# schematic.net
KiCad netlist of a schematic drawn in EAGLE
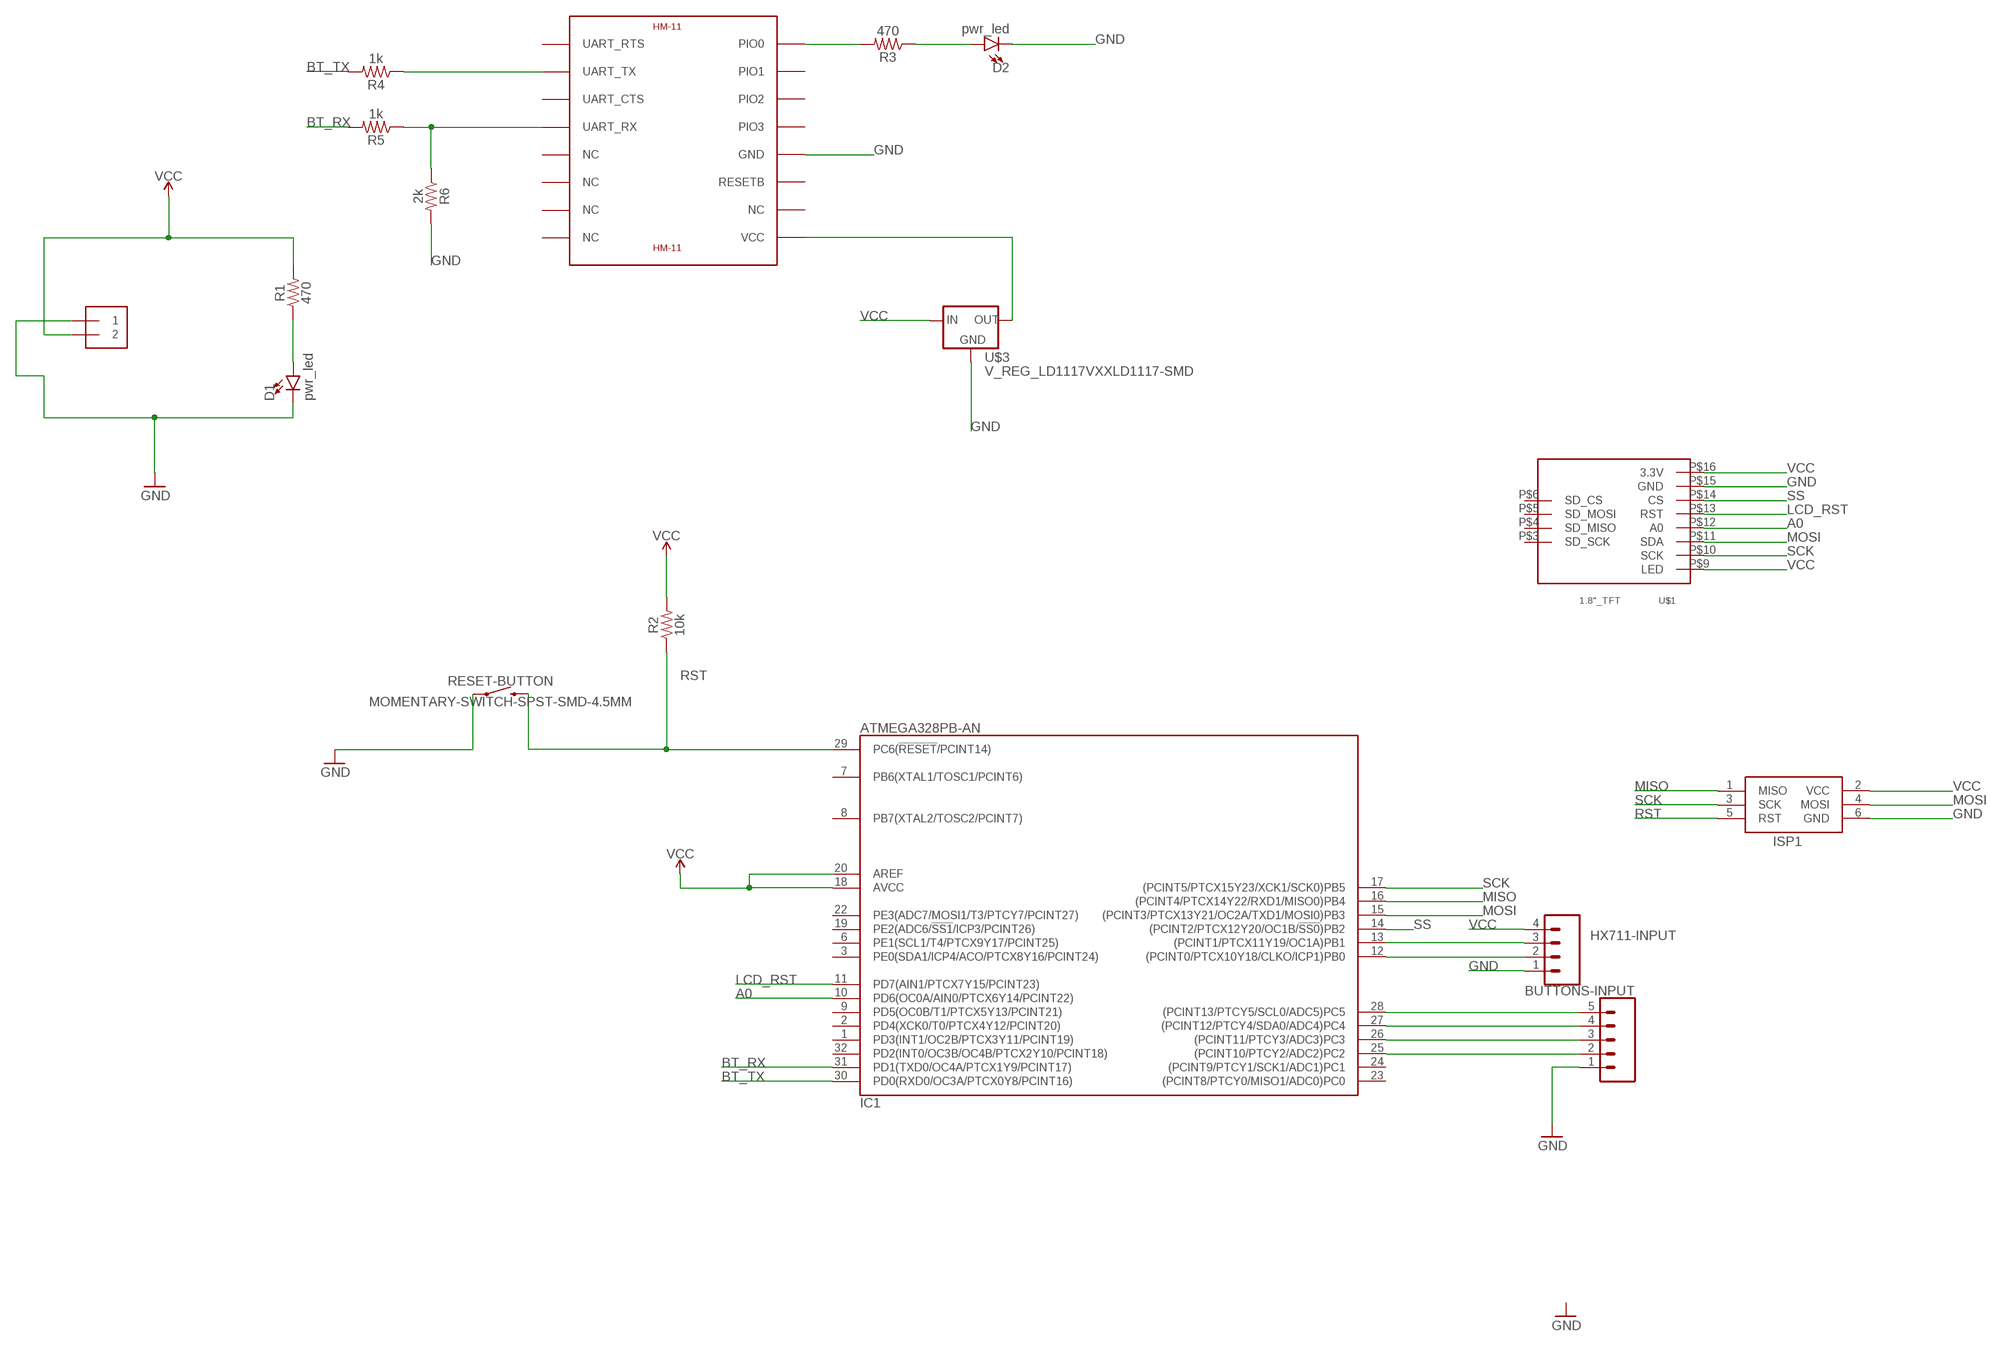
[diagram p0: schematic, sheet 1]

(export (version "E")
  (design (tool "Eeschema 10.0.6"))
  (components
    (comp (ref "BUTTONS-INPUT")
      (value "CONN_05")
      (footprint "eagle-import:1X05")
      (libsource (lib "eagle-import") (part "CONN_05"))
    )
    (comp (ref "D1")
      (value "pwr_led")
      (footprint "eagle-import:LED-1206")
      (libsource (lib "eagle-import") (part "LED1206"))
    )
    (comp (ref "D2")
      (value "pwr_led")
      (footprint "eagle-import:LED-1206")
      (libsource (lib "eagle-import") (part "LED1206"))
    )
    (comp (ref "HX711-INPUT")
      (value "CONN_04LONGPADS")
      (footprint "eagle-import:1X04_LONGPADS")
      (libsource (lib "eagle-import") (part "CONN_04LONGPADS"))
    )
    (comp (ref "IC1")
      (value "ATMEGA328PB-AN")
      (footprint "eagle-import:QFP32_7X7_0.80")
      (libsource (lib "eagle-import") (part "ATMEGA328PB-AN"))
    )
    (comp (ref "ISP1")
      (value "AVRISP-BOX")
      (footprint "eagle-import:AVRISP-BOX")
      (libsource (lib "eagle-import") (part "AVRISP-BOX"))
    )
    (comp (ref "PWR")
      (value "1X2-3.5MM")
      (footprint "eagle-import:1X2-3.5MM")
      (libsource (lib "eagle-import") (part "1X2-3.5MM"))
    )
    (comp (ref "R1")
      (value "470")
      (footprint "eagle-import:1206")
      (libsource (lib "eagle-import") (part "RESISTOR1206"))
    )
    (comp (ref "R2")
      (value "10k")
      (footprint "eagle-import:1206")
      (libsource (lib "eagle-import") (part "RESISTOR1206"))
    )
    (comp (ref "R3")
      (value "470")
      (footprint "eagle-import:1206")
      (libsource (lib "eagle-import") (part "RESISTOR1206"))
    )
    (comp (ref "R4")
      (value "1k")
      (footprint "eagle-import:1206")
      (libsource (lib "eagle-import") (part "RESISTOR1206"))
    )
    (comp (ref "R5")
      (value "1k")
      (footprint "eagle-import:1206")
      (libsource (lib "eagle-import") (part "RESISTOR1206"))
    )
    (comp (ref "R6")
      (value "2k")
      (footprint "eagle-import:1206")
      (libsource (lib "eagle-import") (part "RESISTOR1206"))
    )
    (comp (ref "RESET-BUTTON")
      (value "MOMENTARY-SWITCH-SPST-SMD-4.5MM")
      (footprint "eagle-import:TACTILE_SWITCH_SMD_4.5MM")
      (libsource (lib "eagle-import") (part "MOMENTARY-SWITCH-SPST-SMD-4.5MM"))
    )
    (comp (ref "U$1")
      (value "1.8\"_TFT")
      (footprint "eagle-import:1.8__TFT")
      (libsource (lib "eagle-import") (part "1.8{dblquote}_TFT"))
    )
    (comp (ref "U$2")
      (value "HM-11")
      (footprint "eagle-import:HM-11")
      (libsource (lib "eagle-import") (part "HM-11"))
    )
    (comp (ref "U$3")
      (value "V_REG_LD1117VXXLD1117-SMD")
      (footprint "eagle-import:SOT223")
      (libsource (lib "eagle-import") (part "V_REG_LD1117VXXLD1117-SMD"))
    )
  )
  (nets
    (net (code "1") (name "/A0") (class "Default")
      (node (ref "IC1") (pin "10") (pinfunction "PD6(OC0A/AIN0/PTCX6Y14/PCINT22)_10") (pintype "bidirectional"))
      (node (ref "U$1") (pin "P$12") (pinfunction "A0_P$12") (pintype "bidirectional"))
    )
    (net (code "2") (name "/BT_RX") (class "Default")
      (node (ref "IC1") (pin "31") (pinfunction "PD1(TXD0/OC4A/PTCX1Y9/PCINT17)_31") (pintype "bidirectional"))
      (node (ref "R5") (pin "2") (pinfunction "2_2") (pintype "passive"))
    )
    (net (code "3") (name "/BT_TX") (class "Default")
      (node (ref "IC1") (pin "30") (pinfunction "PD0(RXD0/OC3A/PTCX0Y8/PCINT16)_30") (pintype "bidirectional"))
      (node (ref "R4") (pin "2") (pinfunction "2_2") (pintype "passive"))
    )
    (net (code "4") (name "/LCD_RST") (class "Default")
      (node (ref "IC1") (pin "11") (pinfunction "PD7(AIN1/PTCX7Y15/PCINT23)_11") (pintype "bidirectional"))
      (node (ref "U$1") (pin "P$13") (pinfunction "RST_P$13") (pintype "bidirectional"))
    )
    (net (code "5") (name "/MISO") (class "Default")
      (node (ref "IC1") (pin "16") (pinfunction "(PCINT4/PTCX14Y22/RXD1/MISO0)PB4_16") (pintype "bidirectional"))
      (node (ref "ISP1") (pin "1") (pinfunction "MISO_1") (pintype "input"))
    )
    (net (code "6") (name "/MOSI") (class "Default")
      (node (ref "IC1") (pin "15") (pinfunction "(PCINT3/PTCX13Y21/OC2A/TXD1/MOSI0)PB3_15") (pintype "bidirectional"))
      (node (ref "ISP1") (pin "4") (pinfunction "MOSI_4") (pintype "output"))
      (node (ref "U$1") (pin "P$11") (pinfunction "SDA_P$11") (pintype "bidirectional"))
    )
    (net (code "7") (name "/RST") (class "Default")
      (node (ref "IC1") (pin "29") (pinfunction "PC6(~{RESET}/PCINT14)_29") (pintype "bidirectional"))
      (node (ref "ISP1") (pin "5") (pinfunction "RST_5") (pintype "output"))
      (node (ref "R2") (pin "1") (pinfunction "1_1") (pintype "passive"))
      (node (ref "RESET-BUTTON") (pin "1") (pinfunction "2_1") (pintype "passive"))
      (node (ref "RESET-BUTTON") (pin "4") (pinfunction "2_4") (pintype "passive"))
    )
    (net (code "8") (name "/SCK") (class "Default")
      (node (ref "IC1") (pin "17") (pinfunction "(PCINT5/PTCX15Y23/XCK1/SCK0)PB5_17") (pintype "bidirectional"))
      (node (ref "ISP1") (pin "3") (pinfunction "SCK_3") (pintype "output"))
      (node (ref "U$1") (pin "P$10") (pinfunction "SCK_P$10") (pintype "bidirectional"))
    )
    (net (code "9") (name "/SS") (class "Default")
      (node (ref "IC1") (pin "14") (pinfunction "(PCINT2/PTCX12Y20/OC1B/~{SS0})PB2_14") (pintype "bidirectional"))
      (node (ref "U$1") (pin "P$14") (pinfunction "CS_P$14") (pintype "bidirectional"))
    )
    (net (code "10") (name "GND") (class "Default")
      (node (ref "BUTTONS-INPUT") (pin "1") (pinfunction "1_1") (pintype "passive"))
      (node (ref "D1") (pin "C") (pinfunction "C_C") (pintype "passive"))
      (node (ref "D2") (pin "C") (pinfunction "C_C") (pintype "passive"))
      (node (ref "HX711-INPUT") (pin "1") (pinfunction "1_1") (pintype "passive"))
      (node (ref "ISP1") (pin "6") (pinfunction "GND_6") (pintype "power_in"))
      (node (ref "PWR") (pin "1") (pinfunction "1_1") (pintype "passive"))
      (node (ref "R6") (pin "2") (pinfunction "2_2") (pintype "passive"))
      (node (ref "RESET-BUTTON") (pin "2") (pinfunction "1_2") (pintype "passive"))
      (node (ref "RESET-BUTTON") (pin "3") (pinfunction "1_3") (pintype "passive"))
      (node (ref "U$1") (pin "P$15") (pinfunction "GND_P$15") (pintype "bidirectional"))
      (node (ref "U$2") (pin "GND") (pinfunction "GND_GND") (pintype "bidirectional"))
      (node (ref "U$3") (pin "1") (pinfunction "GND_1") (pintype "input"))
    )
    (net (code "11") (name "Net-(D1-PadA)") (class "Default")
      (node (ref "D1") (pin "A") (pinfunction "A_A") (pintype "passive"))
      (node (ref "R1") (pin "1") (pinfunction "1_1") (pintype "passive"))
    )
    (net (code "12") (name "Net-(D2-PadA)") (class "Default")
      (node (ref "D2") (pin "A") (pinfunction "A_A") (pintype "passive"))
      (node (ref "R3") (pin "1") (pinfunction "1_1") (pintype "passive"))
    )
    (net (code "13") (name "Net-(IC1A-(PCINT0{slash}PTCX10Y18{slash}CLKO{slash}ICP1)PB0)") (class "Default")
      (node (ref "HX711-INPUT") (pin "2") (pinfunction "2_2") (pintype "passive"))
      (node (ref "IC1") (pin "12") (pinfunction "(PCINT0/PTCX10Y18/CLKO/ICP1)PB0_12") (pintype "bidirectional"))
    )
    (net (code "14") (name "Net-(IC1A-(PCINT1{slash}PTCX11Y19{slash}OC1A)PB1)") (class "Default")
      (node (ref "HX711-INPUT") (pin "3") (pinfunction "3_3") (pintype "passive"))
      (node (ref "IC1") (pin "13") (pinfunction "(PCINT1/PTCX11Y19/OC1A)PB1_13") (pintype "bidirectional"))
    )
    (net (code "15") (name "Net-(IC1A-(PCINT10{slash}PTCY2{slash}ADC2)PC2)") (class "Default")
      (node (ref "BUTTONS-INPUT") (pin "2") (pinfunction "2_2") (pintype "passive"))
      (node (ref "IC1") (pin "25") (pinfunction "(PCINT10/PTCY2/ADC2)PC2_25") (pintype "bidirectional"))
    )
    (net (code "16") (name "Net-(IC1A-(PCINT11{slash}PTCY3{slash}ADC3)PC3)") (class "Default")
      (node (ref "BUTTONS-INPUT") (pin "3") (pinfunction "3_3") (pintype "passive"))
      (node (ref "IC1") (pin "26") (pinfunction "(PCINT11/PTCY3/ADC3)PC3_26") (pintype "bidirectional"))
    )
    (net (code "17") (name "Net-(IC1A-(PCINT12{slash}PTCY4{slash}SDA0{slash}ADC4)PC4)") (class "Default")
      (node (ref "BUTTONS-INPUT") (pin "4") (pinfunction "4_4") (pintype "passive"))
      (node (ref "IC1") (pin "27") (pinfunction "(PCINT12/PTCY4/SDA0/ADC4)PC4_27") (pintype "bidirectional"))
    )
    (net (code "18") (name "Net-(IC1A-(PCINT13{slash}PTCY5{slash}SCL0{slash}ADC5)PC5)") (class "Default")
      (node (ref "BUTTONS-INPUT") (pin "5") (pinfunction "5_5") (pintype "passive"))
      (node (ref "IC1") (pin "28") (pinfunction "(PCINT13/PTCY5/SCL0/ADC5)PC5_28") (pintype "bidirectional"))
    )
    (net (code "19") (name "Net-(R3-Pad2)") (class "Default")
      (node (ref "R3") (pin "2") (pinfunction "2_2") (pintype "passive"))
      (node (ref "U$2") (pin "PIO0") (pinfunction "PIO0_PIO0") (pintype "bidirectional"))
    )
    (net (code "20") (name "Net-(R4-Pad1)") (class "Default")
      (node (ref "R4") (pin "1") (pinfunction "1_1") (pintype "passive"))
      (node (ref "U$2") (pin "UART_TX") (pinfunction "UART_TX_UART_TX") (pintype "bidirectional"))
    )
    (net (code "21") (name "Net-(R5-Pad1)") (class "Default")
      (node (ref "R5") (pin "1") (pinfunction "1_1") (pintype "passive"))
      (node (ref "R6") (pin "1") (pinfunction "1_1") (pintype "passive"))
      (node (ref "U$2") (pin "UART_RX") (pinfunction "UART_RX_UART_RX") (pintype "bidirectional"))
    )
    (net (code "22") (name "Net-(U$3-OUT)") (class "Default")
      (node (ref "U$2") (pin "VCC") (pinfunction "VCC_VCC") (pintype "bidirectional"))
      (node (ref "U$3") (pin "2") (pinfunction "OUT_2") (pintype "passive"))
    )
    (net (code "23") (name "VCC") (class "Default")
      (node (ref "HX711-INPUT") (pin "4") (pinfunction "4_4") (pintype "passive"))
      (node (ref "IC1") (pin "18") (pinfunction "AVCC_18") (pintype "power_in"))
      (node (ref "IC1") (pin "20") (pinfunction "AREF_20") (pintype "passive"))
      (node (ref "ISP1") (pin "2") (pinfunction "VCC_2") (pintype "power_in"))
      (node (ref "PWR") (pin "2") (pinfunction "2_2") (pintype "passive"))
      (node (ref "R1") (pin "2") (pinfunction "2_2") (pintype "passive"))
      (node (ref "R2") (pin "2") (pinfunction "2_2") (pintype "passive"))
      (node (ref "U$1") (pin "P$16") (pinfunction "3.3V_P$16") (pintype "bidirectional"))
      (node (ref "U$1") (pin "P$9") (pinfunction "LED_P$9") (pintype "bidirectional"))
      (node (ref "U$3") (pin "3") (pinfunction "IN_3") (pintype "input"))
    )
    (net (code "24") (name "unconnected-(IC1A-(PCINT8{slash}PTCY0{slash}MISO1{slash}ADC0)PC0-Pad23)") (class "Default")
      (node (ref "IC1") (pin "23") (pinfunction "(PCINT8/PTCY0/MISO1/ADC0)PC0_23") (pintype "bidirectional"))
    )
    (net (code "25") (name "unconnected-(IC1A-(PCINT9{slash}PTCY1{slash}SCK1{slash}ADC1)PC1-Pad24)") (class "Default")
      (node (ref "IC1") (pin "24") (pinfunction "(PCINT9/PTCY1/SCK1/ADC1)PC1_24") (pintype "bidirectional"))
    )
    (net (code "26") (name "unconnected-(IC1A-PB6(XTAL1{slash}TOSC1{slash}PCINT6)-Pad7)") (class "Default")
      (node (ref "IC1") (pin "7") (pinfunction "PB6(XTAL1/TOSC1/PCINT6)_7") (pintype "bidirectional"))
    )
    (net (code "27") (name "unconnected-(IC1A-PB7(XTAL2{slash}TOSC2{slash}PCINT7)-Pad8)") (class "Default")
      (node (ref "IC1") (pin "8") (pinfunction "PB7(XTAL2/TOSC2/PCINT7)_8") (pintype "bidirectional"))
    )
    (net (code "28") (name "unconnected-(IC1A-PD2(INT0{slash}OC3B{slash}OC4B{slash}PTCX2Y10{slash}PCINT18)-Pad32)") (class "Default")
      (node (ref "IC1") (pin "32") (pinfunction "PD2(INT0/OC3B/OC4B/PTCX2Y10/PCINT18)_32") (pintype "bidirectional"))
    )
    (net (code "29") (name "unconnected-(IC1A-PD3(INT1{slash}OC2B{slash}PTCX3Y11{slash}PCINT19)-Pad1)") (class "Default")
      (node (ref "IC1") (pin "1") (pinfunction "PD3(INT1/OC2B/PTCX3Y11/PCINT19)_1") (pintype "bidirectional"))
    )
    (net (code "30") (name "unconnected-(IC1A-PD4(XCK0{slash}T0{slash}PTCX4Y12{slash}PCINT20)-Pad2)") (class "Default")
      (node (ref "IC1") (pin "2") (pinfunction "PD4(XCK0/T0/PTCX4Y12/PCINT20)_2") (pintype "bidirectional"))
    )
    (net (code "31") (name "unconnected-(IC1A-PD5(OC0B{slash}T1{slash}PTCX5Y13{slash}PCINT21)-Pad9)") (class "Default")
      (node (ref "IC1") (pin "9") (pinfunction "PD5(OC0B/T1/PTCX5Y13/PCINT21)_9") (pintype "bidirectional"))
    )
    (net (code "32") (name "unconnected-(IC1A-PE0(SDA1{slash}ICP4{slash}ACO{slash}PTCX8Y16{slash}PCINT24)-Pad3)") (class "Default")
      (node (ref "IC1") (pin "3") (pinfunction "PE0(SDA1/ICP4/ACO/PTCX8Y16/PCINT24)_3") (pintype "bidirectional"))
    )
    (net (code "33") (name "unconnected-(IC1A-PE1(SCL1{slash}T4{slash}PTCX9Y17{slash}PCINT25)-Pad6)") (class "Default")
      (node (ref "IC1") (pin "6") (pinfunction "PE1(SCL1/T4/PTCX9Y17/PCINT25)_6") (pintype "bidirectional"))
    )
    (net (code "34") (name "unconnected-(IC1A-PE2(ADC6{slash}~{SS1}{slash}ICP3{slash}PCINT26)-Pad19)") (class "Default")
      (node (ref "IC1") (pin "19") (pinfunction "PE2(ADC6/~{SS1}/ICP3/PCINT26)_19") (pintype "bidirectional"))
    )
    (net (code "35") (name "unconnected-(IC1A-PE3(ADC7{slash}MOSI1{slash}T3{slash}PTCY7{slash}PCINT27)-Pad22)") (class "Default")
      (node (ref "IC1") (pin "22") (pinfunction "PE3(ADC7/MOSI1/T3/PTCY7/PCINT27)_22") (pintype "bidirectional"))
    )
    (net (code "36") (name "unconnected-(U$1-SD_CS-PadP$6)") (class "Default")
      (node (ref "U$1") (pin "P$6") (pinfunction "SD_CS_P$6") (pintype "bidirectional"))
    )
    (net (code "37") (name "unconnected-(U$1-SD_MISO-PadP$4)") (class "Default")
      (node (ref "U$1") (pin "P$4") (pinfunction "SD_MISO_P$4") (pintype "bidirectional"))
    )
    (net (code "38") (name "unconnected-(U$1-SD_MOSI-PadP$5)") (class "Default")
      (node (ref "U$1") (pin "P$5") (pinfunction "SD_MOSI_P$5") (pintype "bidirectional"))
    )
    (net (code "39") (name "unconnected-(U$1-SD_SCK-PadP$3)") (class "Default")
      (node (ref "U$1") (pin "P$3") (pinfunction "SD_SCK_P$3") (pintype "bidirectional"))
    )
    (net (code "40") (name "unconnected-(U$2-NC-PadNC@5)") (class "Default")
      (node (ref "U$2") (pin "NC@5") (pinfunction "NC_NC@5") (pintype "bidirectional"))
    )
    (net (code "41") (name "unconnected-(U$2-NC-PadNC@6)") (class "Default")
      (node (ref "U$2") (pin "NC@6") (pinfunction "NC_NC@6") (pintype "bidirectional"))
    )
    (net (code "42") (name "unconnected-(U$2-NC-PadNC@7)") (class "Default")
      (node (ref "U$2") (pin "NC@7") (pinfunction "NC_NC@7") (pintype "bidirectional"))
    )
    (net (code "43") (name "unconnected-(U$2-NC-PadNC@8)") (class "Default")
      (node (ref "U$2") (pin "NC@8") (pinfunction "NC_NC@8") (pintype "bidirectional"))
    )
    (net (code "44") (name "unconnected-(U$2-NC-PadNC@10)") (class "Default")
      (node (ref "U$2") (pin "NC@10") (pinfunction "NC_NC@10") (pintype "bidirectional"))
    )
    (net (code "45") (name "unconnected-(U$2-PadPIO1)") (class "Default")
      (node (ref "U$2") (pin "PIO1") (pinfunction "PIO1_PIO1") (pintype "bidirectional"))
    )
    (net (code "46") (name "unconnected-(U$2-PadPIO2)") (class "Default")
      (node (ref "U$2") (pin "PIO2") (pinfunction "PIO2_PIO2") (pintype "bidirectional"))
    )
    (net (code "47") (name "unconnected-(U$2-PadPIO3)") (class "Default")
      (node (ref "U$2") (pin "PIO3") (pinfunction "PIO3_PIO3") (pintype "bidirectional"))
    )
    (net (code "48") (name "unconnected-(U$2-PadRESETB)") (class "Default")
      (node (ref "U$2") (pin "RESETB") (pinfunction "RESETB_RESETB") (pintype "bidirectional"))
    )
    (net (code "49") (name "unconnected-(U$2-PadUART_CTS)") (class "Default")
      (node (ref "U$2") (pin "UART_CTS") (pinfunction "UART_CTS_UART_CTS") (pintype "bidirectional"))
    )
    (net (code "50") (name "unconnected-(U$2-PadUART_RTS)") (class "Default")
      (node (ref "U$2") (pin "UART_RTS") (pinfunction "UART_RTS_UART_RTS") (pintype "bidirectional"))
    )
  )
)
